# Mini_BDM_Pod_RevB.net
KiCad netlist of a schematic drawn in EAGLE
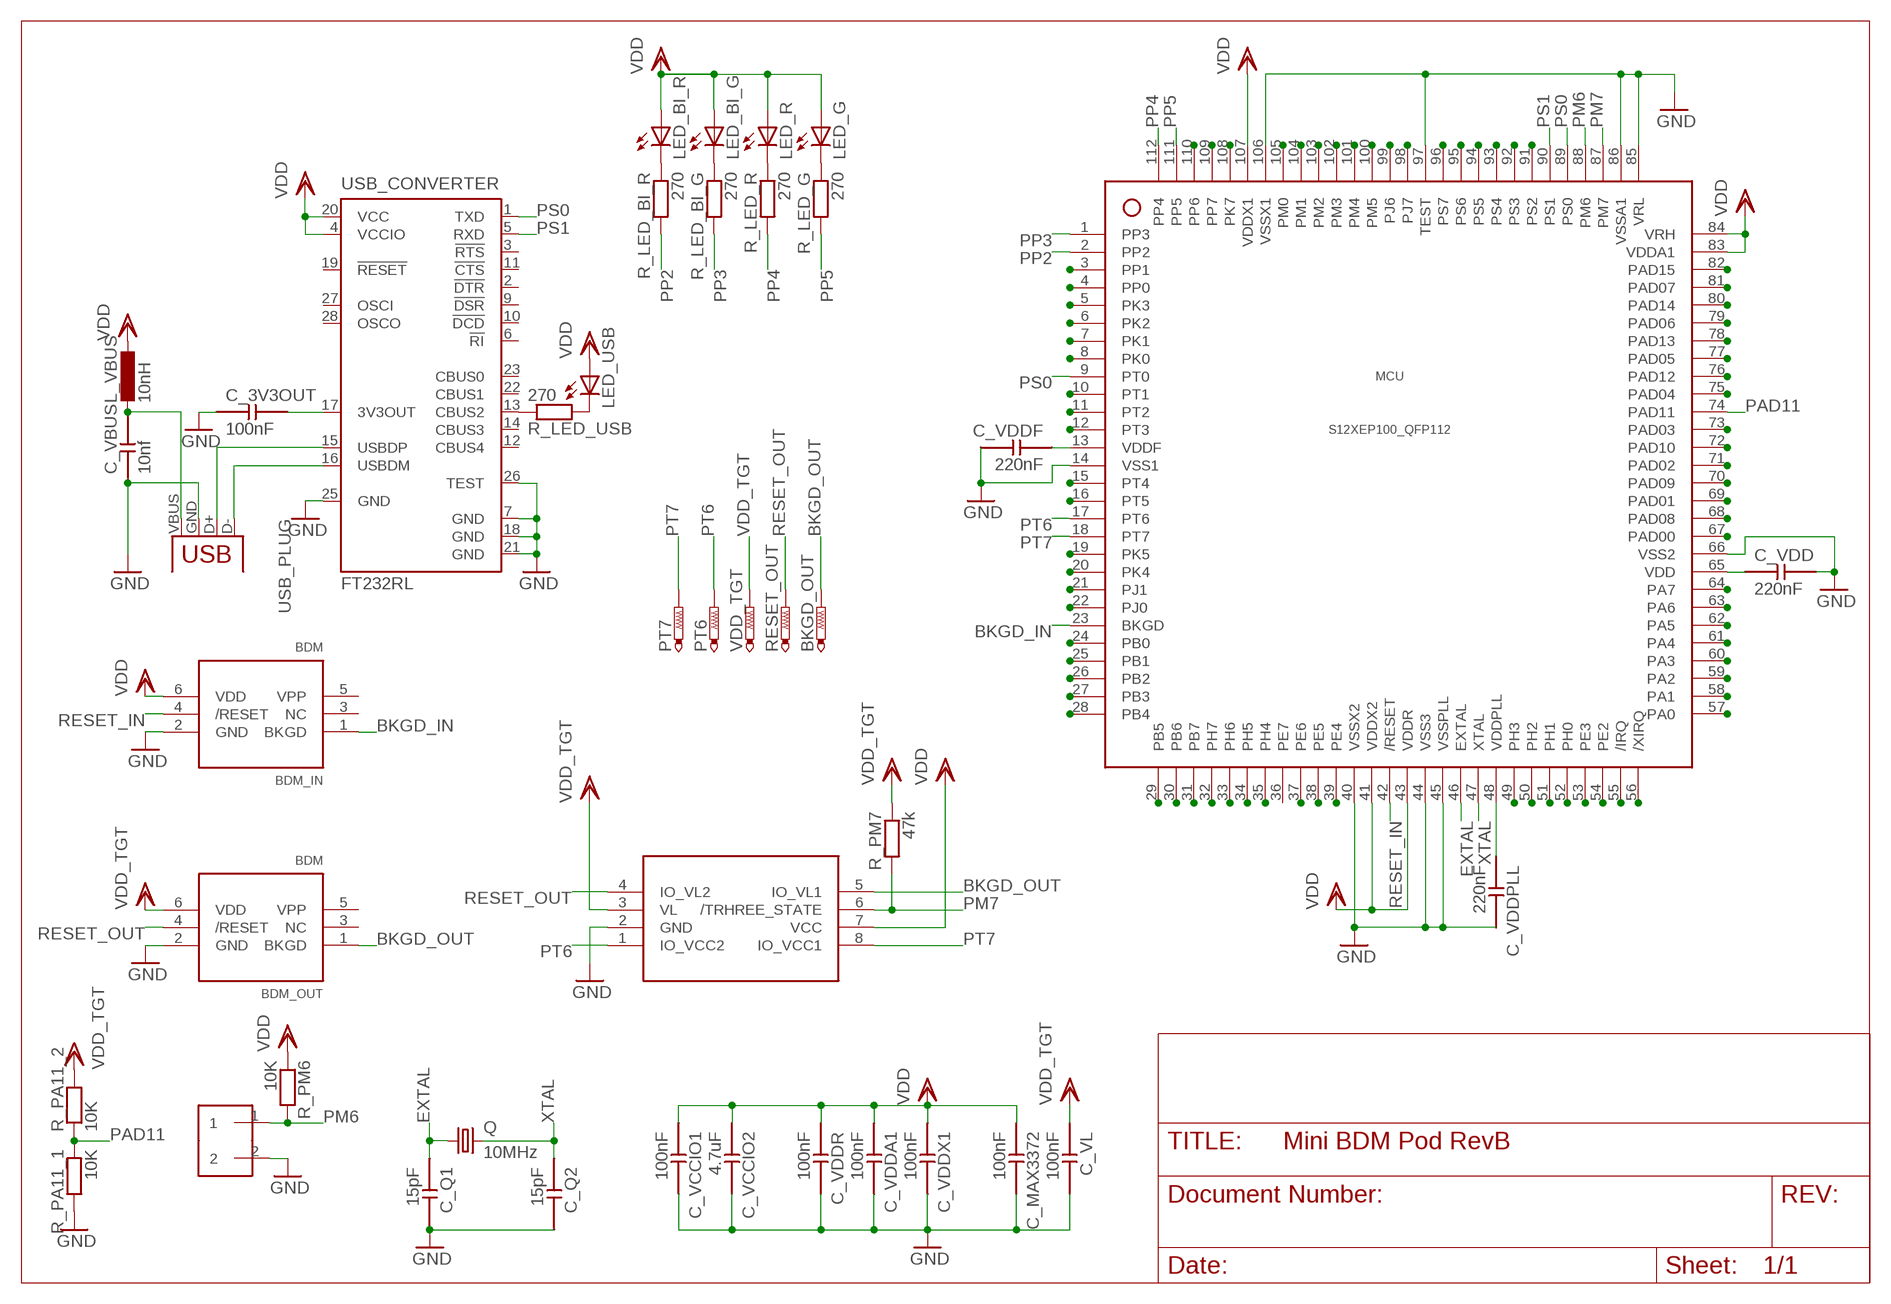
[diagram p0: schematic, sheet 1]

(export (version "E")
  (design (tool "Eeschema 10.0.6"))
  (components
    (comp (ref "BDM_IN")
      (value "BDM")
      (footprint "eagle-import:BDM")
      (libsource (lib "eagle-import") (part "BDM"))
    )
    (comp (ref "BDM_OUT")
      (value "BDM")
      (footprint "eagle-import:BDM")
      (libsource (lib "eagle-import") (part "BDM"))
    )
    (comp (ref "BKGD_OUT")
      (value "PTR1TP10R")
      (footprint "eagle-import:TP10R")
      (libsource (lib "eagle-import") (part "PTR1TP10R"))
    )
    (comp (ref "C_3V3OUT")
      (value "100nF")
      (footprint "eagle-import:0805")
      (libsource (lib "eagle-import") (part "C"))
    )
    (comp (ref "C_MAX3372")
      (value "100nF")
      (footprint "eagle-import:0805")
      (libsource (lib "eagle-import") (part "C"))
    )
    (comp (ref "C_Q1")
      (value "15pF")
      (footprint "eagle-import:0805")
      (libsource (lib "eagle-import") (part "C"))
    )
    (comp (ref "C_Q2")
      (value "15pF")
      (footprint "eagle-import:0805")
      (libsource (lib "eagle-import") (part "C"))
    )
    (comp (ref "C_VBUS")
      (value "10nf")
      (footprint "eagle-import:0805")
      (libsource (lib "eagle-import") (part "C"))
    )
    (comp (ref "C_VCCIO1")
      (value "100nF")
      (footprint "eagle-import:0805")
      (libsource (lib "eagle-import") (part "C"))
    )
    (comp (ref "C_VCCIO2")
      (value "4.7uF")
      (footprint "eagle-import:0805")
      (libsource (lib "eagle-import") (part "C"))
    )
    (comp (ref "C_VDD")
      (value "220nF")
      (footprint "eagle-import:0805")
      (libsource (lib "eagle-import") (part "C"))
    )
    (comp (ref "C_VDDA1")
      (value "100nF")
      (footprint "eagle-import:0805")
      (libsource (lib "eagle-import") (part "C"))
    )
    (comp (ref "C_VDDF")
      (value "220nF")
      (footprint "eagle-import:0805")
      (libsource (lib "eagle-import") (part "C"))
    )
    (comp (ref "C_VDDPLL")
      (value "220nF")
      (footprint "eagle-import:0805")
      (libsource (lib "eagle-import") (part "C"))
    )
    (comp (ref "C_VDDR")
      (value "100nF")
      (footprint "eagle-import:0805")
      (libsource (lib "eagle-import") (part "C"))
    )
    (comp (ref "C_VDDX1")
      (value "100nF")
      (footprint "eagle-import:0805")
      (libsource (lib "eagle-import") (part "C"))
    )
    (comp (ref "C_VL")
      (value "100nF")
      (footprint "eagle-import:0805")
      (libsource (lib "eagle-import") (part "C"))
    )
    (comp (ref "JUMPER")
      (value "1X2")
      (footprint "eagle-import:1X2")
      (libsource (lib "eagle-import") (part "1X2"))
    )
    (comp (ref "LED_BI_G")
      (value "LED0805")
      (footprint "eagle-import:0805")
      (libsource (lib "eagle-import") (part "LED0805"))
    )
    (comp (ref "LED_BI_R")
      (value "LED0805")
      (footprint "eagle-import:0805")
      (libsource (lib "eagle-import") (part "LED0805"))
    )
    (comp (ref "LED_G")
      (value "LED0805")
      (footprint "eagle-import:0805")
      (libsource (lib "eagle-import") (part "LED0805"))
    )
    (comp (ref "LED_R")
      (value "LED0805")
      (footprint "eagle-import:0805")
      (libsource (lib "eagle-import") (part "LED0805"))
    )
    (comp (ref "LED_USB")
      (value "LED0805")
      (footprint "eagle-import:0805")
      (libsource (lib "eagle-import") (part "LED0805"))
    )
    (comp (ref "LEVEL_SHIFTER")
      (value "MAX3373")
      (footprint "eagle-import:SOT-23-MAXIM")
      (libsource (lib "eagle-import") (part "MAX3373"))
    )
    (comp (ref "L_VBUS")
      (value "10nH")
      (footprint "eagle-import:0805")
      (libsource (lib "eagle-import") (part "L0805"))
    )
    (comp (ref "MCU")
      (value "S12XEP100_QFP112")
      (footprint "eagle-import:QFP112")
      (libsource (lib "eagle-import") (part "S12XEP100_QFP112"))
    )
    (comp (ref "PT6")
      (value "PTR1TP10R")
      (footprint "eagle-import:TP10R")
      (libsource (lib "eagle-import") (part "PTR1TP10R"))
    )
    (comp (ref "PT7")
      (value "PTR1TP10R")
      (footprint "eagle-import:TP10R")
      (libsource (lib "eagle-import") (part "PTR1TP10R"))
    )
    (comp (ref "Q")
      (value "10MHz")
      (footprint "eagle-import:HC49U70")
      (libsource (lib "eagle-import") (part "CRYSTALHC49U70"))
    )
    (comp (ref "RESET_OUT")
      (value "PTR1TP10R")
      (footprint "eagle-import:TP10R")
      (libsource (lib "eagle-import") (part "PTR1TP10R"))
    )
    (comp (ref "R_LED_BI_G")
      (value "270")
      (footprint "eagle-import:0805")
      (libsource (lib "eagle-import") (part "R"))
    )
    (comp (ref "R_LED_BI_R")
      (value "270")
      (footprint "eagle-import:0805")
      (libsource (lib "eagle-import") (part "R"))
    )
    (comp (ref "R_LED_G")
      (value "270")
      (footprint "eagle-import:0805")
      (libsource (lib "eagle-import") (part "R"))
    )
    (comp (ref "R_LED_R")
      (value "270")
      (footprint "eagle-import:0805")
      (libsource (lib "eagle-import") (part "R"))
    )
    (comp (ref "R_LED_USB")
      (value "270")
      (footprint "eagle-import:0805")
      (libsource (lib "eagle-import") (part "R"))
    )
    (comp (ref "R_PA11_1")
      (value "10K")
      (footprint "eagle-import:0805")
      (libsource (lib "eagle-import") (part "R"))
    )
    (comp (ref "R_PA11_2")
      (value "10K")
      (footprint "eagle-import:0805")
      (libsource (lib "eagle-import") (part "R"))
    )
    (comp (ref "R_PM6")
      (value "10K")
      (footprint "eagle-import:0805")
      (libsource (lib "eagle-import") (part "R"))
    )
    (comp (ref "R_PM7")
      (value "47k")
      (footprint "eagle-import:0805")
      (libsource (lib "eagle-import") (part "R"))
    )
    (comp (ref "USB_CONVERTER")
      (value "FT232RL")
      (footprint "eagle-import:SSOP28")
      (libsource (lib "eagle-import") (part "FT232RL"))
    )
    (comp (ref "USB_PLUG")
      (value "USB_PRINT-A")
      (footprint "eagle-import:A")
      (libsource (lib "eagle-import") (part "USB_PRINT-A"))
    )
    (comp (ref "VDD_TGT")
      (value "PTR1TP10R")
      (footprint "eagle-import:TP10R")
      (libsource (lib "eagle-import") (part "PTR1TP10R"))
    )
  )
  (nets
    (net (code "1") (name "/BKGD_IN") (class "Default")
      (node (ref "BDM_IN") (pin "1") (pinfunction "BKGD_1") (pintype "bidirectional"))
      (node (ref "MCU") (pin "23") (pinfunction "BKGD_23") (pintype "input"))
    )
    (net (code "2") (name "/BKGD_OUT") (class "Default")
      (node (ref "BDM_OUT") (pin "1") (pinfunction "BKGD_1") (pintype "bidirectional"))
      (node (ref "BKGD_OUT") (pin "TP") (pinfunction "TP_TP") (pintype "input"))
      (node (ref "LEVEL_SHIFTER") (pin "5") (pinfunction "IO_VL1_5") (pintype "bidirectional"))
    )
    (net (code "3") (name "/EXTAL") (class "Default")
      (node (ref "C_Q1") (pin "2") (pinfunction "2_2") (pintype "passive"))
      (node (ref "MCU") (pin "46") (pinfunction "EXTAL_46") (pintype "input"))
      (node (ref "Q") (pin "1") (pinfunction "1_1") (pintype "passive"))
    )
    (net (code "4") (name "/PAD11") (class "Default")
      (node (ref "MCU") (pin "74") (pinfunction "PAD11_74") (pintype "bidirectional"))
      (node (ref "R_PA11_1") (pin "2") (pinfunction "2_2") (pintype "passive"))
      (node (ref "R_PA11_2") (pin "2") (pinfunction "2_2") (pintype "passive"))
    )
    (net (code "5") (name "/PM6") (class "Default")
      (node (ref "JUMPER") (pin "1") (pinfunction "1_1") (pintype "bidirectional"))
      (node (ref "MCU") (pin "88") (pinfunction "PM6_88") (pintype "bidirectional"))
      (node (ref "R_PM6") (pin "1") (pinfunction "1_1") (pintype "passive"))
    )
    (net (code "6") (name "/PM7") (class "Default")
      (node (ref "LEVEL_SHIFTER") (pin "6") (pinfunction "/TRHREE_STATE_6") (pintype "bidirectional"))
      (node (ref "MCU") (pin "87") (pinfunction "PM7_87") (pintype "bidirectional"))
      (node (ref "R_PM7") (pin "1") (pinfunction "1_1") (pintype "passive"))
    )
    (net (code "7") (name "/PP2") (class "Default")
      (node (ref "MCU") (pin "2") (pinfunction "PP2_2") (pintype "bidirectional"))
      (node (ref "R_LED_BI_R") (pin "1") (pinfunction "1_1") (pintype "passive"))
    )
    (net (code "8") (name "/PP3") (class "Default")
      (node (ref "MCU") (pin "1") (pinfunction "PP3_1") (pintype "bidirectional"))
      (node (ref "R_LED_BI_G") (pin "1") (pinfunction "1_1") (pintype "passive"))
    )
    (net (code "9") (name "/PP4") (class "Default")
      (node (ref "MCU") (pin "112") (pinfunction "PP4_112") (pintype "bidirectional"))
      (node (ref "R_LED_R") (pin "1") (pinfunction "1_1") (pintype "passive"))
    )
    (net (code "10") (name "/PP5") (class "Default")
      (node (ref "MCU") (pin "111") (pinfunction "PP5_111") (pintype "bidirectional"))
      (node (ref "R_LED_G") (pin "1") (pinfunction "1_1") (pintype "passive"))
    )
    (net (code "11") (name "/PS0") (class "Default")
      (node (ref "MCU") (pin "89") (pinfunction "PS0_89") (pintype "bidirectional"))
      (node (ref "MCU") (pin "9") (pinfunction "PT0_9") (pintype "bidirectional"))
      (node (ref "USB_CONVERTER") (pin "1") (pinfunction "TXD_1") (pintype "output"))
    )
    (net (code "12") (name "/PS1") (class "Default")
      (node (ref "MCU") (pin "90") (pinfunction "PS1_90") (pintype "bidirectional"))
      (node (ref "USB_CONVERTER") (pin "5") (pinfunction "RXD_5") (pintype "input"))
    )
    (net (code "13") (name "/PT6") (class "Default")
      (node (ref "LEVEL_SHIFTER") (pin "1") (pinfunction "IO_VCC2_1") (pintype "bidirectional"))
      (node (ref "MCU") (pin "17") (pinfunction "PT6_17") (pintype "bidirectional"))
      (node (ref "PT6") (pin "TP") (pinfunction "TP_TP") (pintype "input"))
    )
    (net (code "14") (name "/PT7") (class "Default")
      (node (ref "LEVEL_SHIFTER") (pin "8") (pinfunction "IO_VCC1_8") (pintype "bidirectional"))
      (node (ref "MCU") (pin "18") (pinfunction "PT7_18") (pintype "bidirectional"))
      (node (ref "PT7") (pin "TP") (pinfunction "TP_TP") (pintype "input"))
    )
    (net (code "15") (name "/RESET_IN") (class "Default")
      (node (ref "BDM_IN") (pin "4") (pinfunction "/RESET_4") (pintype "bidirectional"))
      (node (ref "MCU") (pin "42") (pinfunction "/RESET_42") (pintype "output"))
    )
    (net (code "16") (name "/RESET_OUT") (class "Default")
      (node (ref "BDM_OUT") (pin "4") (pinfunction "/RESET_4") (pintype "bidirectional"))
      (node (ref "LEVEL_SHIFTER") (pin "4") (pinfunction "IO_VL2_4") (pintype "bidirectional"))
      (node (ref "RESET_OUT") (pin "TP") (pinfunction "TP_TP") (pintype "input"))
    )
    (net (code "17") (name "/XTAL") (class "Default")
      (node (ref "C_Q2") (pin "2") (pinfunction "2_2") (pintype "passive"))
      (node (ref "MCU") (pin "47") (pinfunction "XTAL_47") (pintype "output"))
      (node (ref "Q") (pin "2") (pinfunction "2_2") (pintype "passive"))
    )
    (net (code "18") (name "GND") (class "Default")
      (node (ref "BDM_IN") (pin "2") (pinfunction "GND_2") (pintype "power_in"))
      (node (ref "BDM_OUT") (pin "2") (pinfunction "GND_2") (pintype "power_in"))
      (node (ref "C_3V3OUT") (pin "2") (pinfunction "2_2") (pintype "passive"))
      (node (ref "C_MAX3372") (pin "1") (pinfunction "1_1") (pintype "passive"))
      (node (ref "C_Q1") (pin "1") (pinfunction "1_1") (pintype "passive"))
      (node (ref "C_Q2") (pin "1") (pinfunction "1_1") (pintype "passive"))
      (node (ref "C_VBUS") (pin "2") (pinfunction "2_2") (pintype "passive"))
      (node (ref "C_VCCIO1") (pin "1") (pinfunction "1_1") (pintype "passive"))
      (node (ref "C_VCCIO2") (pin "1") (pinfunction "1_1") (pintype "passive"))
      (node (ref "C_VDD") (pin "1") (pinfunction "1_1") (pintype "passive"))
      (node (ref "C_VDDA1") (pin "1") (pinfunction "1_1") (pintype "passive"))
      (node (ref "C_VDDF") (pin "1") (pinfunction "1_1") (pintype "passive"))
      (node (ref "C_VDDPLL") (pin "1") (pinfunction "1_1") (pintype "passive"))
      (node (ref "C_VDDR") (pin "1") (pinfunction "1_1") (pintype "passive"))
      (node (ref "C_VDDX1") (pin "1") (pinfunction "1_1") (pintype "passive"))
      (node (ref "C_VL") (pin "1") (pinfunction "1_1") (pintype "passive"))
      (node (ref "JUMPER") (pin "2") (pinfunction "2_2") (pintype "bidirectional"))
      (node (ref "LEVEL_SHIFTER") (pin "2") (pinfunction "GND_2") (pintype "power_in"))
      (node (ref "MCU") (pin "106") (pinfunction "VSSX1_106") (pintype "power_in"))
      (node (ref "MCU") (pin "14") (pinfunction "VSS1_14") (pintype "power_in"))
      (node (ref "MCU") (pin "40") (pinfunction "VSSX2_40") (pintype "power_in"))
      (node (ref "MCU") (pin "44") (pinfunction "VSS3_44") (pintype "power_in"))
      (node (ref "MCU") (pin "45") (pinfunction "VSSPLL_45") (pintype "power_in"))
      (node (ref "MCU") (pin "66") (pinfunction "VSS2_66") (pintype "power_in"))
      (node (ref "MCU") (pin "85") (pinfunction "VRL_85") (pintype "power_in"))
      (node (ref "MCU") (pin "86") (pinfunction "VSSA1_86") (pintype "power_in"))
      (node (ref "MCU") (pin "97") (pinfunction "TEST_97") (pintype "input"))
      (node (ref "R_PA11_1") (pin "1") (pinfunction "1_1") (pintype "passive"))
      (node (ref "USB_CONVERTER") (pin "18") (pinfunction "GND_18") (pintype "power_in"))
      (node (ref "USB_CONVERTER") (pin "21") (pinfunction "GND_21") (pintype "power_in"))
      (node (ref "USB_CONVERTER") (pin "25") (pinfunction "GND_25") (pintype "power_in"))
      (node (ref "USB_CONVERTER") (pin "26") (pinfunction "TEST_26") (pintype "input"))
      (node (ref "USB_CONVERTER") (pin "7") (pinfunction "GND_7") (pintype "power_in"))
      (node (ref "USB_PLUG") (pin "GND") (pinfunction "VBUS_GND") (pintype "bidirectional"))
    )
    (net (code "19") (name "Net-(LED_BI_G-C)") (class "Default")
      (node (ref "LED_BI_G") (pin "2") (pinfunction "C_2") (pintype "passive"))
      (node (ref "R_LED_BI_G") (pin "2") (pinfunction "2_2") (pintype "passive"))
    )
    (net (code "20") (name "Net-(LED_BI_R-C)") (class "Default")
      (node (ref "LED_BI_R") (pin "2") (pinfunction "C_2") (pintype "passive"))
      (node (ref "R_LED_BI_R") (pin "2") (pinfunction "2_2") (pintype "passive"))
    )
    (net (code "21") (name "Net-(LED_G-C)") (class "Default")
      (node (ref "LED_G") (pin "2") (pinfunction "C_2") (pintype "passive"))
      (node (ref "R_LED_G") (pin "2") (pinfunction "2_2") (pintype "passive"))
    )
    (net (code "22") (name "Net-(LED_R-C)") (class "Default")
      (node (ref "LED_R") (pin "2") (pinfunction "C_2") (pintype "passive"))
      (node (ref "R_LED_R") (pin "2") (pinfunction "2_2") (pintype "passive"))
    )
    (net (code "23") (name "Net-(LED_USB-C)") (class "Default")
      (node (ref "LED_USB") (pin "2") (pinfunction "C_2") (pintype "passive"))
      (node (ref "R_LED_USB") (pin "1") (pinfunction "1_1") (pintype "passive"))
    )
    (net (code "24") (name "Net-(MCU-VDD)") (class "Default")
      (node (ref "C_VDD") (pin "2") (pinfunction "2_2") (pintype "passive"))
      (node (ref "MCU") (pin "65") (pinfunction "VDD_65") (pintype "power_in"))
    )
    (net (code "25") (name "Net-(MCU-VDDF)") (class "Default")
      (node (ref "C_VDDF") (pin "2") (pinfunction "2_2") (pintype "passive"))
      (node (ref "MCU") (pin "13") (pinfunction "VDDF_13") (pintype "power_in"))
    )
    (net (code "26") (name "Net-(MCU-VDDPLL)") (class "Default")
      (node (ref "C_VDDPLL") (pin "2") (pinfunction "2_2") (pintype "passive"))
      (node (ref "MCU") (pin "48") (pinfunction "VDDPLL_48") (pintype "power_in"))
    )
    (net (code "27") (name "Net-(USB_CONVERTER-3V3OUT)") (class "Default")
      (node (ref "C_3V3OUT") (pin "1") (pinfunction "1_1") (pintype "passive"))
      (node (ref "USB_CONVERTER") (pin "17") (pinfunction "3V3OUT_17") (pintype "output"))
    )
    (net (code "28") (name "Net-(USB_CONVERTER-CBUS2)") (class "Default")
      (node (ref "R_LED_USB") (pin "2") (pinfunction "2_2") (pintype "passive"))
      (node (ref "USB_CONVERTER") (pin "13") (pinfunction "CBUS2_13") (pintype "bidirectional"))
    )
    (net (code "29") (name "Net-(USB_CONVERTER-USBDM)") (class "Default")
      (node (ref "USB_CONVERTER") (pin "16") (pinfunction "USBDM_16") (pintype "bidirectional"))
      (node (ref "USB_PLUG") (pin "D-") (pinfunction "D+_D-") (pintype "bidirectional"))
    )
    (net (code "30") (name "Net-(USB_CONVERTER-USBDP)") (class "Default")
      (node (ref "USB_CONVERTER") (pin "15") (pinfunction "USBDP_15") (pintype "bidirectional"))
      (node (ref "USB_PLUG") (pin "D+") (pinfunction "D-_D+") (pintype "bidirectional"))
    )
    (net (code "31") (name "Net-(USB_PLUG-GND)") (class "Default")
      (node (ref "C_VBUS") (pin "1") (pinfunction "1_1") (pintype "passive"))
      (node (ref "L_VBUS") (pin "2") (pinfunction "2_2") (pintype "passive"))
      (node (ref "USB_PLUG") (pin "VBUS") (pinfunction "GND_VBUS") (pintype "bidirectional"))
    )
    (net (code "32") (name "VDD") (class "Default")
      (node (ref "BDM_IN") (pin "6") (pinfunction "VDD_6") (pintype "power_in"))
      (node (ref "C_MAX3372") (pin "2") (pinfunction "2_2") (pintype "passive"))
      (node (ref "C_VCCIO1") (pin "2") (pinfunction "2_2") (pintype "passive"))
      (node (ref "C_VCCIO2") (pin "2") (pinfunction "2_2") (pintype "passive"))
      (node (ref "C_VDDA1") (pin "2") (pinfunction "2_2") (pintype "passive"))
      (node (ref "C_VDDR") (pin "2") (pinfunction "2_2") (pintype "passive"))
      (node (ref "C_VDDX1") (pin "2") (pinfunction "2_2") (pintype "passive"))
      (node (ref "LED_BI_G") (pin "1") (pinfunction "A_1") (pintype "passive"))
      (node (ref "LED_BI_R") (pin "1") (pinfunction "A_1") (pintype "passive"))
      (node (ref "LED_G") (pin "1") (pinfunction "A_1") (pintype "passive"))
      (node (ref "LED_R") (pin "1") (pinfunction "A_1") (pintype "passive"))
      (node (ref "LED_USB") (pin "1") (pinfunction "A_1") (pintype "passive"))
      (node (ref "LEVEL_SHIFTER") (pin "7") (pinfunction "VCC_7") (pintype "power_in"))
      (node (ref "L_VBUS") (pin "1") (pinfunction "1_1") (pintype "passive"))
      (node (ref "MCU") (pin "107") (pinfunction "VDDX1_107") (pintype "power_in"))
      (node (ref "MCU") (pin "41") (pinfunction "VDDX2_41") (pintype "power_in"))
      (node (ref "MCU") (pin "43") (pinfunction "VDDR_43") (pintype "power_in"))
      (node (ref "MCU") (pin "83") (pinfunction "VDDA1_83") (pintype "power_in"))
      (node (ref "MCU") (pin "84") (pinfunction "VRH_84") (pintype "power_in"))
      (node (ref "R_PM6") (pin "2") (pinfunction "2_2") (pintype "passive"))
      (node (ref "USB_CONVERTER") (pin "20") (pinfunction "VCC_20") (pintype "power_in"))
      (node (ref "USB_CONVERTER") (pin "4") (pinfunction "VCCIO_4") (pintype "power_in"))
    )
    (net (code "33") (name "VDD_TGT") (class "Default")
      (node (ref "BDM_OUT") (pin "6") (pinfunction "VDD_6") (pintype "power_in"))
      (node (ref "C_VL") (pin "2") (pinfunction "2_2") (pintype "passive"))
      (node (ref "LEVEL_SHIFTER") (pin "3") (pinfunction "VL_3") (pintype "bidirectional"))
      (node (ref "R_PA11_2") (pin "1") (pinfunction "1_1") (pintype "passive"))
      (node (ref "R_PM7") (pin "2") (pinfunction "2_2") (pintype "passive"))
      (node (ref "VDD_TGT") (pin "TP") (pinfunction "TP_TP") (pintype "input"))
    )
    (net (code "34") (name "unconnected-(BDM_IN-NC-Pad3)") (class "Default")
      (node (ref "BDM_IN") (pin "3") (pinfunction "NC_3") (pintype "no_connect"))
    )
    (net (code "35") (name "unconnected-(BDM_IN-VPP-Pad5)") (class "Default")
      (node (ref "BDM_IN") (pin "5") (pinfunction "VPP_5") (pintype "no_connect"))
    )
    (net (code "36") (name "unconnected-(BDM_OUT-NC-Pad3)") (class "Default")
      (node (ref "BDM_OUT") (pin "3") (pinfunction "NC_3") (pintype "no_connect"))
    )
    (net (code "37") (name "unconnected-(BDM_OUT-VPP-Pad5)") (class "Default")
      (node (ref "BDM_OUT") (pin "5") (pinfunction "VPP_5") (pintype "no_connect"))
    )
    (net (code "38") (name "unconnected-(MCU-PA0-Pad57)") (class "Default")
      (node (ref "MCU") (pin "57") (pinfunction "PA0_57") (pintype "bidirectional"))
    )
    (net (code "39") (name "unconnected-(MCU-PA1-Pad58)") (class "Default")
      (node (ref "MCU") (pin "58") (pinfunction "PA1_58") (pintype "bidirectional"))
    )
    (net (code "40") (name "unconnected-(MCU-PA2-Pad59)") (class "Default")
      (node (ref "MCU") (pin "59") (pinfunction "PA2_59") (pintype "bidirectional"))
    )
    (net (code "41") (name "unconnected-(MCU-PA3-Pad60)") (class "Default")
      (node (ref "MCU") (pin "60") (pinfunction "PA3_60") (pintype "bidirectional"))
    )
    (net (code "42") (name "unconnected-(MCU-PA4-Pad61)") (class "Default")
      (node (ref "MCU") (pin "61") (pinfunction "PA4_61") (pintype "bidirectional"))
    )
    (net (code "43") (name "unconnected-(MCU-PA5-Pad62)") (class "Default")
      (node (ref "MCU") (pin "62") (pinfunction "PA5_62") (pintype "bidirectional"))
    )
    (net (code "44") (name "unconnected-(MCU-PA6-Pad63)") (class "Default")
      (node (ref "MCU") (pin "63") (pinfunction "PA6_63") (pintype "bidirectional"))
    )
    (net (code "45") (name "unconnected-(MCU-PA7-Pad64)") (class "Default")
      (node (ref "MCU") (pin "64") (pinfunction "PA7_64") (pintype "bidirectional"))
    )
    (net (code "46") (name "unconnected-(MCU-PAD00-Pad67)") (class "Default")
      (node (ref "MCU") (pin "67") (pinfunction "PAD00_67") (pintype "bidirectional"))
    )
    (net (code "47") (name "unconnected-(MCU-PAD01-Pad69)") (class "Default")
      (node (ref "MCU") (pin "69") (pinfunction "PAD01_69") (pintype "bidirectional"))
    )
    (net (code "48") (name "unconnected-(MCU-PAD02-Pad71)") (class "Default")
      (node (ref "MCU") (pin "71") (pinfunction "PAD02_71") (pintype "bidirectional"))
    )
    (net (code "49") (name "unconnected-(MCU-PAD03-Pad73)") (class "Default")
      (node (ref "MCU") (pin "73") (pinfunction "PAD03_73") (pintype "bidirectional"))
    )
    (net (code "50") (name "unconnected-(MCU-PAD04-Pad75)") (class "Default")
      (node (ref "MCU") (pin "75") (pinfunction "PAD04_75") (pintype "bidirectional"))
    )
    (net (code "51") (name "unconnected-(MCU-PAD05-Pad77)") (class "Default")
      (node (ref "MCU") (pin "77") (pinfunction "PAD05_77") (pintype "bidirectional"))
    )
    (net (code "52") (name "unconnected-(MCU-PAD06-Pad79)") (class "Default")
      (node (ref "MCU") (pin "79") (pinfunction "PAD06_79") (pintype "bidirectional"))
    )
    (net (code "53") (name "unconnected-(MCU-PAD07-Pad81)") (class "Default")
      (node (ref "MCU") (pin "81") (pinfunction "PAD07_81") (pintype "bidirectional"))
    )
    (net (code "54") (name "unconnected-(MCU-PAD08-Pad68)") (class "Default")
      (node (ref "MCU") (pin "68") (pinfunction "PAD08_68") (pintype "bidirectional"))
    )
    (net (code "55") (name "unconnected-(MCU-PAD09-Pad70)") (class "Default")
      (node (ref "MCU") (pin "70") (pinfunction "PAD09_70") (pintype "bidirectional"))
    )
    (net (code "56") (name "unconnected-(MCU-PAD10-Pad72)") (class "Default")
      (node (ref "MCU") (pin "72") (pinfunction "PAD10_72") (pintype "bidirectional"))
    )
    (net (code "57") (name "unconnected-(MCU-PAD12-Pad76)") (class "Default")
      (node (ref "MCU") (pin "76") (pinfunction "PAD12_76") (pintype "bidirectional"))
    )
    (net (code "58") (name "unconnected-(MCU-PAD13-Pad78)") (class "Default")
      (node (ref "MCU") (pin "78") (pinfunction "PAD13_78") (pintype "bidirectional"))
    )
    (net (code "59") (name "unconnected-(MCU-PAD14-Pad80)") (class "Default")
      (node (ref "MCU") (pin "80") (pinfunction "PAD14_80") (pintype "bidirectional"))
    )
    (net (code "60") (name "unconnected-(MCU-PAD15-Pad82)") (class "Default")
      (node (ref "MCU") (pin "82") (pinfunction "PAD15_82") (pintype "bidirectional"))
    )
    (net (code "61") (name "unconnected-(MCU-PB0-Pad24)") (class "Default")
      (node (ref "MCU") (pin "24") (pinfunction "PB0_24") (pintype "bidirectional"))
    )
    (net (code "62") (name "unconnected-(MCU-PB1-Pad25)") (class "Default")
      (node (ref "MCU") (pin "25") (pinfunction "PB1_25") (pintype "bidirectional"))
    )
    (net (code "63") (name "unconnected-(MCU-PB2-Pad26)") (class "Default")
      (node (ref "MCU") (pin "26") (pinfunction "PB2_26") (pintype "bidirectional"))
    )
    (net (code "64") (name "unconnected-(MCU-PB3-Pad27)") (class "Default")
      (node (ref "MCU") (pin "27") (pinfunction "PB3_27") (pintype "bidirectional"))
    )
    (net (code "65") (name "unconnected-(MCU-PB4-Pad28)") (class "Default")
      (node (ref "MCU") (pin "28") (pinfunction "PB4_28") (pintype "bidirectional"))
    )
    (net (code "66") (name "unconnected-(MCU-PB5-Pad29)") (class "Default")
      (node (ref "MCU") (pin "29") (pinfunction "PB5_29") (pintype "bidirectional"))
    )
    (net (code "67") (name "unconnected-(MCU-PB6-Pad30)") (class "Default")
      (node (ref "MCU") (pin "30") (pinfunction "PB6_30") (pintype "bidirectional"))
    )
    (net (code "68") (name "unconnected-(MCU-PB7-Pad31)") (class "Default")
      (node (ref "MCU") (pin "31") (pinfunction "PB7_31") (pintype "bidirectional"))
    )
    (net (code "69") (name "unconnected-(MCU-PE2-Pad54)") (class "Default")
      (node (ref "MCU") (pin "54") (pinfunction "PE2_54") (pintype "bidirectional"))
    )
    (net (code "70") (name "unconnected-(MCU-PE3-Pad53)") (class "Default")
      (node (ref "MCU") (pin "53") (pinfunction "PE3_53") (pintype "bidirectional"))
    )
    (net (code "71") (name "unconnected-(MCU-PE4-Pad39)") (class "Default")
      (node (ref "MCU") (pin "39") (pinfunction "PE4_39") (pintype "bidirectional"))
    )
    (net (code "72") (name "unconnected-(MCU-PE5-Pad38)") (class "Default")
      (node (ref "MCU") (pin "38") (pinfunction "PE5_38") (pintype "bidirectional"))
    )
    (net (code "73") (name "unconnected-(MCU-PE6-Pad37)") (class "Default")
      (node (ref "MCU") (pin "37") (pinfunction "PE6_37") (pintype "bidirectional"))
    )
    (net (code "74") (name "unconnected-(MCU-PE7-Pad36)") (class "Default")
      (node (ref "MCU") (pin "36") (pinfunction "PE7_36") (pintype "bidirectional"))
    )
    (net (code "75") (name "unconnected-(MCU-PH0-Pad52)") (class "Default")
      (node (ref "MCU") (pin "52") (pinfunction "PH0_52") (pintype "bidirectional"))
    )
    (net (code "76") (name "unconnected-(MCU-PH1-Pad51)") (class "Default")
      (node (ref "MCU") (pin "51") (pinfunction "PH1_51") (pintype "bidirectional"))
    )
    (net (code "77") (name "unconnected-(MCU-PH2-Pad50)") (class "Default")
      (node (ref "MCU") (pin "50") (pinfunction "PH2_50") (pintype "bidirectional"))
    )
    (net (code "78") (name "unconnected-(MCU-PH3-Pad49)") (class "Default")
      (node (ref "MCU") (pin "49") (pinfunction "PH3_49") (pintype "bidirectional"))
    )
    (net (code "79") (name "unconnected-(MCU-PH4-Pad35)") (class "Default")
      (node (ref "MCU") (pin "35") (pinfunction "PH4_35") (pintype "bidirectional"))
    )
    (net (code "80") (name "unconnected-(MCU-PH5-Pad34)") (class "Default")
      (node (ref "MCU") (pin "34") (pinfunction "PH5_34") (pintype "bidirectional"))
    )
    (net (code "81") (name "unconnected-(MCU-PH6-Pad33)") (class "Default")
      (node (ref "MCU") (pin "33") (pinfunction "PH6_33") (pintype "bidirectional"))
    )
    (net (code "82") (name "unconnected-(MCU-PH7-Pad32)") (class "Default")
      (node (ref "MCU") (pin "32") (pinfunction "PH7_32") (pintype "bidirectional"))
    )
    (net (code "83") (name "unconnected-(MCU-PJ0-Pad22)") (class "Default")
      (node (ref "MCU") (pin "22") (pinfunction "PJ0_22") (pintype "bidirectional"))
    )
    (net (code "84") (name "unconnected-(MCU-PJ1-Pad21)") (class "Default")
      (node (ref "MCU") (pin "21") (pinfunction "PJ1_21") (pintype "bidirectional"))
    )
    (net (code "85") (name "unconnected-(MCU-PJ6-Pad99)") (class "Default")
      (node (ref "MCU") (pin "99") (pinfunction "PJ6_99") (pintype "bidirectional"))
    )
    (net (code "86") (name "unconnected-(MCU-PJ7-Pad98)") (class "Default")
      (node (ref "MCU") (pin "98") (pinfunction "PJ7_98") (pintype "bidirectional"))
    )
    (net (code "87") (name "unconnected-(MCU-PK0-Pad8)") (class "Default")
      (node (ref "MCU") (pin "8") (pinfunction "PK0_8") (pintype "bidirectional"))
    )
    (net (code "88") (name "unconnected-(MCU-PK1-Pad7)") (class "Default")
      (node (ref "MCU") (pin "7") (pinfunction "PK1_7") (pintype "bidirectional"))
    )
    (net (code "89") (name "unconnected-(MCU-PK2-Pad6)") (class "Default")
      (node (ref "MCU") (pin "6") (pinfunction "PK2_6") (pintype "bidirectional"))
    )
    (net (code "90") (name "unconnected-(MCU-PK3-Pad5)") (class "Default")
      (node (ref "MCU") (pin "5") (pinfunction "PK3_5") (pintype "bidirectional"))
    )
    (net (code "91") (name "unconnected-(MCU-PK4-Pad20)") (class "Default")
      (node (ref "MCU") (pin "20") (pinfunction "PK4_20") (pintype "bidirectional"))
    )
    (net (code "92") (name "unconnected-(MCU-PK5-Pad19)") (class "Default")
      (node (ref "MCU") (pin "19") (pinfunction "PK5_19") (pintype "bidirectional"))
    )
    (net (code "93") (name "unconnected-(MCU-PK7-Pad108)") (class "Default")
      (node (ref "MCU") (pin "108") (pinfunction "PK7_108") (pintype "bidirectional"))
    )
    (net (code "94") (name "unconnected-(MCU-PM0-Pad105)") (class "Default")
      (node (ref "MCU") (pin "105") (pinfunction "PM0_105") (pintype "bidirectional"))
    )
    (net (code "95") (name "unconnected-(MCU-PM1-Pad104)") (class "Default")
      (node (ref "MCU") (pin "104") (pinfunction "PM1_104") (pintype "bidirectional"))
    )
    (net (code "96") (name "unconnected-(MCU-PM2-Pad103)") (class "Default")
      (node (ref "MCU") (pin "103") (pinfunction "PM2_103") (pintype "bidirectional"))
    )
    (net (code "97") (name "unconnected-(MCU-PM3-Pad102)") (class "Default")
      (node (ref "MCU") (pin "102") (pinfunction "PM3_102") (pintype "bidirectional"))
    )
    (net (code "98") (name "unconnected-(MCU-PM4-Pad101)") (class "Default")
      (node (ref "MCU") (pin "101") (pinfunction "PM4_101") (pintype "bidirectional"))
    )
    (net (code "99") (name "unconnected-(MCU-PM5-Pad100)") (class "Default")
      (node (ref "MCU") (pin "100") (pinfunction "PM5_100") (pintype "bidirectional"))
    )
    (net (code "100") (name "unconnected-(MCU-PP0-Pad4)") (class "Default")
      (node (ref "MCU") (pin "4") (pinfunction "PP0_4") (pintype "bidirectional"))
    )
    (net (code "101") (name "unconnected-(MCU-PP1-Pad3)") (class "Default")
      (node (ref "MCU") (pin "3") (pinfunction "PP1_3") (pintype "bidirectional"))
    )
    (net (code "102") (name "unconnected-(MCU-PP6-Pad110)") (class "Default")
      (node (ref "MCU") (pin "110") (pinfunction "PP6_110") (pintype "bidirectional"))
    )
    (net (code "103") (name "unconnected-(MCU-PP7-Pad109)") (class "Default")
      (node (ref "MCU") (pin "109") (pinfunction "PP7_109") (pintype "bidirectional"))
    )
    (net (code "104") (name "unconnected-(MCU-PS2-Pad91)") (class "Default")
      (node (ref "MCU") (pin "91") (pinfunction "PS2_91") (pintype "bidirectional"))
    )
    (net (code "105") (name "unconnected-(MCU-PS3-Pad92)") (class "Default")
      (node (ref "MCU") (pin "92") (pinfunction "PS3_92") (pintype "bidirectional"))
    )
    (net (code "106") (name "unconnected-(MCU-PS4-Pad93)") (class "Default")
      (node (ref "MCU") (pin "93") (pinfunction "PS4_93") (pintype "bidirectional"))
    )
    (net (code "107") (name "unconnected-(MCU-PS5-Pad94)") (class "Default")
      (node (ref "MCU") (pin "94") (pinfunction "PS5_94") (pintype "bidirectional"))
    )
    (net (code "108") (name "unconnected-(MCU-PS6-Pad95)") (class "Default")
      (node (ref "MCU") (pin "95") (pinfunction "PS6_95") (pintype "bidirectional"))
    )
    (net (code "109") (name "unconnected-(MCU-PS7-Pad96)") (class "Default")
      (node (ref "MCU") (pin "96") (pinfunction "PS7_96") (pintype "bidirectional"))
    )
    (net (code "110") (name "unconnected-(MCU-PT1-Pad10)") (class "Default")
      (node (ref "MCU") (pin "10") (pinfunction "PT1_10") (pintype "bidirectional"))
    )
    (net (code "111") (name "unconnected-(MCU-PT2-Pad11)") (class "Default")
      (node (ref "MCU") (pin "11") (pinfunction "PT2_11") (pintype "bidirectional"))
    )
    (net (code "112") (name "unconnected-(MCU-PT3-Pad12)") (class "Default")
      (node (ref "MCU") (pin "12") (pinfunction "PT3_12") (pintype "bidirectional"))
    )
    (net (code "113") (name "unconnected-(MCU-PT4-Pad15)") (class "Default")
      (node (ref "MCU") (pin "15") (pinfunction "PT4_15") (pintype "bidirectional"))
    )
    (net (code "114") (name "unconnected-(MCU-PT5-Pad16)") (class "Default")
      (node (ref "MCU") (pin "16") (pinfunction "PT5_16") (pintype "bidirectional"))
    )
    (net (code "115") (name "unconnected-(MCU-{slash}IRQ-Pad55)") (class "Default")
      (node (ref "MCU") (pin "55") (pinfunction "/IRQ_55") (pintype "bidirectional"))
    )
    (net (code "116") (name "unconnected-(MCU-{slash}XIRQ-Pad56)") (class "Default")
      (node (ref "MCU") (pin "56") (pinfunction "/XIRQ_56") (pintype "bidirectional"))
    )
    (net (code "117") (name "unconnected-(USB_CONVERTER-CBUS0-Pad23)") (class "Default")
      (node (ref "USB_CONVERTER") (pin "23") (pinfunction "CBUS0_23") (pintype "bidirectional"))
    )
    (net (code "118") (name "unconnected-(USB_CONVERTER-CBUS1-Pad22)") (class "Default")
      (node (ref "USB_CONVERTER") (pin "22") (pinfunction "CBUS1_22") (pintype "bidirectional"))
    )
    (net (code "119") (name "unconnected-(USB_CONVERTER-CBUS3-Pad14)") (class "Default")
      (node (ref "USB_CONVERTER") (pin "14") (pinfunction "CBUS3_14") (pintype "bidirectional"))
    )
    (net (code "120") (name "unconnected-(USB_CONVERTER-CBUS4-Pad12)") (class "Default")
      (node (ref "USB_CONVERTER") (pin "12") (pinfunction "CBUS4_12") (pintype "bidirectional"))
    )
    (net (code "121") (name "unconnected-(USB_CONVERTER-OSCI-Pad27)") (class "Default")
      (node (ref "USB_CONVERTER") (pin "27") (pinfunction "OSCI_27") (pintype "input"))
    )
    (net (code "122") (name "unconnected-(USB_CONVERTER-OSCO-Pad28)") (class "Default")
      (node (ref "USB_CONVERTER") (pin "28") (pinfunction "OSCO_28") (pintype "output"))
    )
    (net (code "123") (name "unconnected-(USB_CONVERTER-~{CTS}-Pad11)") (class "Default")
      (node (ref "USB_CONVERTER") (pin "11") (pinfunction "~{CTS}_11") (pintype "input"))
    )
    (net (code "124") (name "unconnected-(USB_CONVERTER-~{DCD}-Pad10)") (class "Default")
      (node (ref "USB_CONVERTER") (pin "10") (pinfunction "~{DCD}_10") (pintype "input"))
    )
    (net (code "125") (name "unconnected-(USB_CONVERTER-~{DSR}-Pad9)") (class "Default")
      (node (ref "USB_CONVERTER") (pin "9") (pinfunction "~{DSR}_9") (pintype "input"))
    )
    (net (code "126") (name "unconnected-(USB_CONVERTER-~{DTR}-Pad2)") (class "Default")
      (node (ref "USB_CONVERTER") (pin "2") (pinfunction "~{DTR}_2") (pintype "output"))
    )
    (net (code "127") (name "unconnected-(USB_CONVERTER-~{RESET}-Pad19)") (class "Default")
      (node (ref "USB_CONVERTER") (pin "19") (pinfunction "~{RESET}_19") (pintype "input"))
    )
    (net (code "128") (name "unconnected-(USB_CONVERTER-~{RI}-Pad6)") (class "Default")
      (node (ref "USB_CONVERTER") (pin "6") (pinfunction "~{RI}_6") (pintype "input"))
    )
    (net (code "129") (name "unconnected-(USB_CONVERTER-~{RTS}-Pad3)") (class "Default")
      (node (ref "USB_CONVERTER") (pin "3") (pinfunction "~{RTS}_3") (pintype "output"))
    )
  )
)
